# irwin.net
KiCad netlist of a schematic drawn in EAGLE
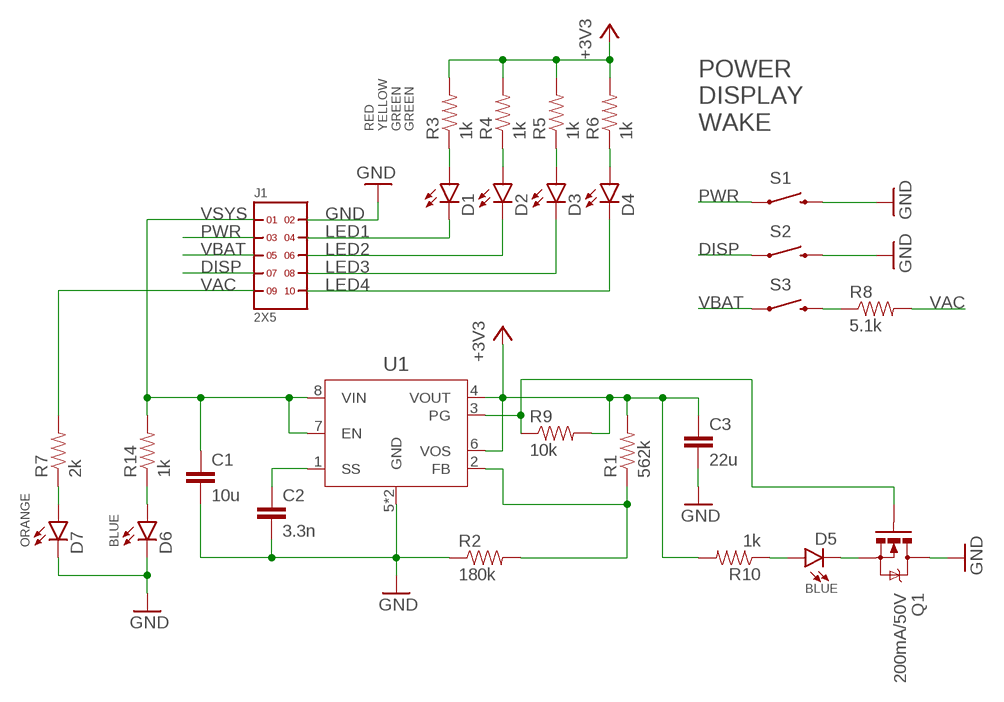
[diagram p0: schematic, sheet 1]

(export (version "E")
  (design (tool "Eeschema 10.0.6"))
  (components
    (comp (ref "C1")
      (value "10u")
      (footprint "eagle-import:1206")
      (libsource (lib "eagle-import") (part "CAP1206"))
    )
    (comp (ref "C2")
      (value "3.3n")
      (footprint "eagle-import:1206")
      (libsource (lib "eagle-import") (part "CAP1206"))
    )
    (comp (ref "C3")
      (value "22u")
      (footprint "eagle-import:1206")
      (libsource (lib "eagle-import") (part "CAP1206"))
    )
    (comp (ref "D1")
      (value "LED1206")
      (footprint "eagle-import:LED-1206")
      (libsource (lib "eagle-import") (part "LED1206"))
    )
    (comp (ref "D2")
      (value "LED1206")
      (footprint "eagle-import:LED-1206")
      (libsource (lib "eagle-import") (part "LED1206"))
    )
    (comp (ref "D3")
      (value "LED1206")
      (footprint "eagle-import:LED-1206")
      (libsource (lib "eagle-import") (part "LED1206"))
    )
    (comp (ref "D4")
      (value "LED1206")
      (footprint "eagle-import:LED-1206")
      (libsource (lib "eagle-import") (part "LED1206"))
    )
    (comp (ref "D5")
      (value "LED1206")
      (footprint "eagle-import:LED-1206")
      (libsource (lib "eagle-import") (part "LED1206"))
    )
    (comp (ref "D6")
      (value "LED1206")
      (footprint "eagle-import:LED-1206")
      (libsource (lib "eagle-import") (part "LED1206"))
    )
    (comp (ref "D7")
      (value "LED1206")
      (footprint "eagle-import:LED-1206")
      (libsource (lib "eagle-import") (part "LED1206"))
    )
    (comp (ref "J1")
      (value "2X5")
      (footprint "eagle-import:2X5")
      (libsource (lib "eagle-import") (part "2X5"))
    )
    (comp (ref "Q1")
      (value "200mA/50V")
      (footprint "eagle-import:SOT23-3")
      (libsource (lib "eagle-import") (part "MOSFET-NCHANNELBSS138"))
    )
    (comp (ref "R1")
      (value "562k")
      (footprint "eagle-import:0805")
      (libsource (lib "eagle-import") (part "RESISTOR0805-RES"))
    )
    (comp (ref "R2")
      (value "180k")
      (footprint "eagle-import:0805")
      (libsource (lib "eagle-import") (part "RESISTOR0805-RES"))
    )
    (comp (ref "R3")
      (value "1k")
      (footprint "eagle-import:1206")
      (libsource (lib "eagle-import") (part "RESISTOR1206"))
    )
    (comp (ref "R4")
      (value "1k")
      (footprint "eagle-import:1206")
      (libsource (lib "eagle-import") (part "RESISTOR1206"))
    )
    (comp (ref "R5")
      (value "1k")
      (footprint "eagle-import:1206")
      (libsource (lib "eagle-import") (part "RESISTOR1206"))
    )
    (comp (ref "R6")
      (value "1k")
      (footprint "eagle-import:1206")
      (libsource (lib "eagle-import") (part "RESISTOR1206"))
    )
    (comp (ref "R7")
      (value "2k")
      (footprint "eagle-import:1206")
      (libsource (lib "eagle-import") (part "RESISTOR1206"))
    )
    (comp (ref "R8")
      (value "5.1k")
      (footprint "eagle-import:0805")
      (libsource (lib "eagle-import") (part "RESISTOR0805-RES"))
    )
    (comp (ref "R9")
      (value "10k")
      (footprint "eagle-import:0805")
      (libsource (lib "eagle-import") (part "RESISTOR0805-RES"))
    )
    (comp (ref "R10")
      (value "1k")
      (footprint "eagle-import:1206")
      (libsource (lib "eagle-import") (part "RESISTOR1206"))
    )
    (comp (ref "R14")
      (value "1k")
      (footprint "eagle-import:1206")
      (libsource (lib "eagle-import") (part "RESISTOR1206"))
    )
    (comp (ref "S1")
      (value "SWITCH-MOMENTARY-2PTH")
      (footprint "eagle-import:TACTILE-PTH")
      (libsource (lib "eagle-import") (part "SWITCH-MOMENTARY-2PTH"))
    )
    (comp (ref "S2")
      (value "SWITCH-MOMENTARY-2PTH")
      (footprint "eagle-import:TACTILE-PTH")
      (libsource (lib "eagle-import") (part "SWITCH-MOMENTARY-2PTH"))
    )
    (comp (ref "S3")
      (value "SWITCH-MOMENTARY-2PTH")
      (footprint "eagle-import:TACTILE-PTH")
      (libsource (lib "eagle-import") (part "SWITCH-MOMENTARY-2PTH"))
    )
    (comp (ref "U1")
      (value "LMZ21700SILR")
      (footprint "eagle-import:SIL0008B")
      (libsource (lib "eagle-import") (part "LMZ21700SILR"))
    )
  )
  (nets
    (net (code "1") (name "+3V3") (class "Default")
      (node (ref "C3") (pin "1") (pinfunction "1_1") (pintype "passive"))
      (node (ref "R1") (pin "2") (pinfunction "2_2") (pintype "passive"))
      (node (ref "R10") (pin "2") (pinfunction "2_2") (pintype "passive"))
      (node (ref "R3") (pin "2") (pinfunction "2_2") (pintype "passive"))
      (node (ref "R4") (pin "2") (pinfunction "2_2") (pintype "passive"))
      (node (ref "R5") (pin "2") (pinfunction "2_2") (pintype "passive"))
      (node (ref "R6") (pin "2") (pinfunction "2_2") (pintype "passive"))
      (node (ref "R9") (pin "2") (pinfunction "2_2") (pintype "passive"))
      (node (ref "U1") (pin "4") (pinfunction "VOUT_4") (pintype "passive"))
      (node (ref "U1") (pin "6") (pinfunction "VOS_6") (pintype "passive"))
    )
    (net (code "2") (name "/DISP") (class "Default")
      (node (ref "J1") (pin "7") (pinfunction "7_7") (pintype "bidirectional"))
      (node (ref "S2") (pin "1") (pinfunction "1_1") (pintype "passive"))
    )
    (net (code "3") (name "/LED1") (class "Default")
      (node (ref "D1") (pin "C") (pinfunction "C_C") (pintype "passive"))
      (node (ref "J1") (pin "4") (pinfunction "4_4") (pintype "bidirectional"))
    )
    (net (code "4") (name "/LED2") (class "Default")
      (node (ref "D2") (pin "C") (pinfunction "C_C") (pintype "passive"))
      (node (ref "J1") (pin "6") (pinfunction "6_6") (pintype "bidirectional"))
    )
    (net (code "5") (name "/LED3") (class "Default")
      (node (ref "D3") (pin "C") (pinfunction "C_C") (pintype "passive"))
      (node (ref "J1") (pin "8") (pinfunction "8_8") (pintype "bidirectional"))
    )
    (net (code "6") (name "/LED4") (class "Default")
      (node (ref "D4") (pin "C") (pinfunction "C_C") (pintype "passive"))
      (node (ref "J1") (pin "10") (pinfunction "10_10") (pintype "bidirectional"))
    )
    (net (code "7") (name "/PWR") (class "Default")
      (node (ref "J1") (pin "3") (pinfunction "3_3") (pintype "bidirectional"))
      (node (ref "S1") (pin "1") (pinfunction "1_1") (pintype "passive"))
    )
    (net (code "8") (name "/VAC") (class "Default")
      (node (ref "J1") (pin "9") (pinfunction "9_9") (pintype "bidirectional"))
      (node (ref "R7") (pin "2") (pinfunction "2_2") (pintype "passive"))
      (node (ref "R8") (pin "2") (pinfunction "2_2") (pintype "passive"))
    )
    (net (code "9") (name "/VBAT") (class "Default")
      (node (ref "J1") (pin "5") (pinfunction "5_5") (pintype "bidirectional"))
      (node (ref "S3") (pin "1") (pinfunction "1_1") (pintype "passive"))
    )
    (net (code "10") (name "/VSYS") (class "Default")
      (node (ref "C1") (pin "1") (pinfunction "1_1") (pintype "passive"))
      (node (ref "J1") (pin "1") (pinfunction "1_1") (pintype "bidirectional"))
      (node (ref "R14") (pin "2") (pinfunction "2_2") (pintype "passive"))
      (node (ref "U1") (pin "7") (pinfunction "EN_7") (pintype "passive"))
      (node (ref "U1") (pin "8") (pinfunction "VIN_8") (pintype "passive"))
    )
    (net (code "11") (name "GND") (class "Default")
      (node (ref "C1") (pin "2") (pinfunction "2_2") (pintype "passive"))
      (node (ref "C2") (pin "2") (pinfunction "2_2") (pintype "passive"))
      (node (ref "C3") (pin "2") (pinfunction "2_2") (pintype "passive"))
      (node (ref "D6") (pin "C") (pinfunction "C_C") (pintype "passive"))
      (node (ref "D7") (pin "C") (pinfunction "C_C") (pintype "passive"))
      (node (ref "J1") (pin "2") (pinfunction "2_2") (pintype "bidirectional"))
      (node (ref "Q1") (pin "3") (pinfunction "D_3") (pintype "passive"))
      (node (ref "R2") (pin "1") (pinfunction "1_1") (pintype "passive"))
      (node (ref "S1") (pin "3") (pinfunction "2_3") (pintype "passive"))
      (node (ref "S2") (pin "3") (pinfunction "2_3") (pintype "passive"))
      (node (ref "U1") (pin "5") (pinfunction "GND_5") (pintype "passive"))
      (node (ref "U1") (pin "9") (pinfunction "GND_9") (pintype "passive"))
    )
    (net (code "12") (name "Net-(D1-PadA)") (class "Default")
      (node (ref "D1") (pin "A") (pinfunction "A_A") (pintype "passive"))
      (node (ref "R3") (pin "1") (pinfunction "1_1") (pintype "passive"))
    )
    (net (code "13") (name "Net-(D2-PadA)") (class "Default")
      (node (ref "D2") (pin "A") (pinfunction "A_A") (pintype "passive"))
      (node (ref "R4") (pin "1") (pinfunction "1_1") (pintype "passive"))
    )
    (net (code "14") (name "Net-(D3-PadA)") (class "Default")
      (node (ref "D3") (pin "A") (pinfunction "A_A") (pintype "passive"))
      (node (ref "R5") (pin "1") (pinfunction "1_1") (pintype "passive"))
    )
    (net (code "15") (name "Net-(D4-PadA)") (class "Default")
      (node (ref "D4") (pin "A") (pinfunction "A_A") (pintype "passive"))
      (node (ref "R6") (pin "1") (pinfunction "1_1") (pintype "passive"))
    )
    (net (code "16") (name "Net-(D5-PadA)") (class "Default")
      (node (ref "D5") (pin "A") (pinfunction "A_A") (pintype "passive"))
      (node (ref "R10") (pin "1") (pinfunction "1_1") (pintype "passive"))
    )
    (net (code "17") (name "Net-(D6-PadA)") (class "Default")
      (node (ref "D6") (pin "A") (pinfunction "A_A") (pintype "passive"))
      (node (ref "R14") (pin "1") (pinfunction "1_1") (pintype "passive"))
    )
    (net (code "18") (name "Net-(D7-PadA)") (class "Default")
      (node (ref "D7") (pin "A") (pinfunction "A_A") (pintype "passive"))
      (node (ref "R7") (pin "1") (pinfunction "1_1") (pintype "passive"))
    )
    (net (code "19") (name "Net-(Q1-G)") (class "Default")
      (node (ref "Q1") (pin "1") (pinfunction "G_1") (pintype "passive"))
      (node (ref "R9") (pin "1") (pinfunction "1_1") (pintype "passive"))
      (node (ref "U1") (pin "3") (pinfunction "PG_3") (pintype "passive"))
    )
    (net (code "20") (name "Net-(Q1-S)") (class "Default")
      (node (ref "D5") (pin "C") (pinfunction "C_C") (pintype "passive"))
      (node (ref "Q1") (pin "2") (pinfunction "S_2") (pintype "passive"))
    )
    (net (code "21") (name "Net-(S3-2)") (class "Default")
      (node (ref "R8") (pin "1") (pinfunction "1_1") (pintype "passive"))
      (node (ref "S3") (pin "3") (pinfunction "2_3") (pintype "passive"))
    )
    (net (code "22") (name "Net-(U1-FB)") (class "Default")
      (node (ref "R1") (pin "1") (pinfunction "1_1") (pintype "passive"))
      (node (ref "R2") (pin "2") (pinfunction "2_2") (pintype "passive"))
      (node (ref "U1") (pin "2") (pinfunction "FB_2") (pintype "passive"))
    )
    (net (code "23") (name "Net-(U1-SS)") (class "Default")
      (node (ref "C2") (pin "1") (pinfunction "1_1") (pintype "passive"))
      (node (ref "U1") (pin "1") (pinfunction "SS_1") (pintype "passive"))
    )
  )
)
